# Interfaces_and_Connectors.net
KiCad netlist of a schematic drawn in Altium Designer
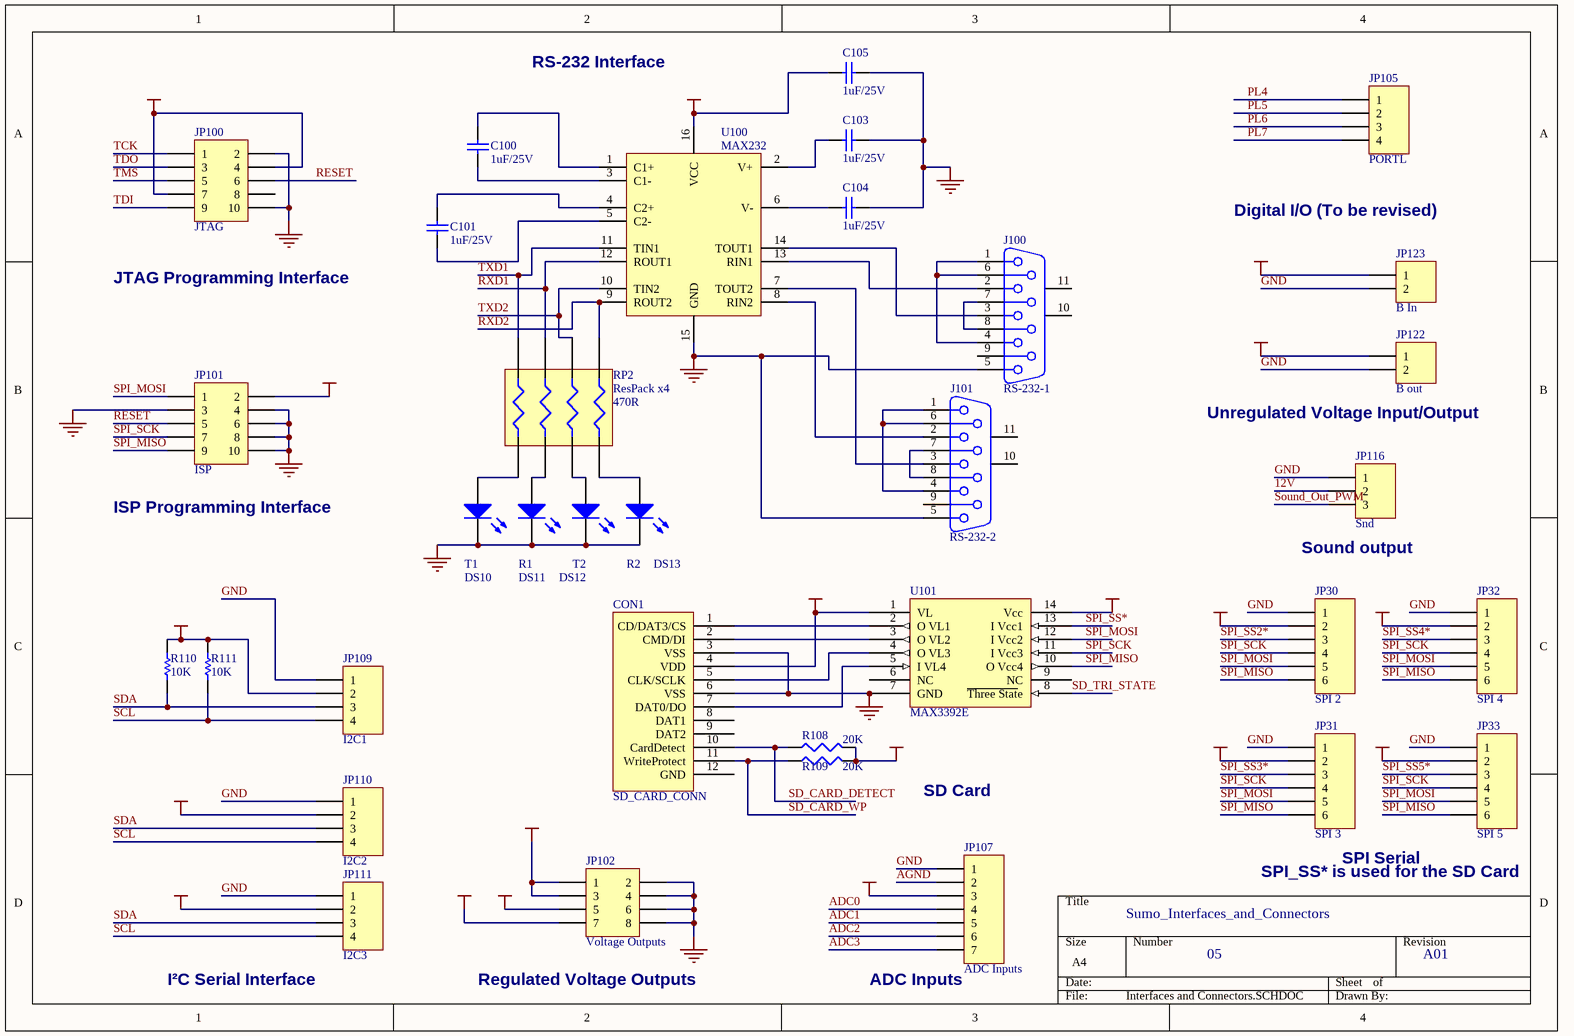
[diagram p0: Interfaces and Connectors.SCHDOC]

(export (version "E")
  (design (tool "Eeschema 10.0.6"))
  (components
    (comp (ref "C100")
      (value "1uF/25V")
      (footprint "CC2012-0805")
      (description "Capacitor (Semiconductor SIM Model)")
      (fields (field (name "Comment") "Cap Semi") (field (name "PUBLISHER") "Altium Limited"))
      (libsource (lib "Miscellaneous Devices") (part "Cap Semi"))
    )
    (comp (ref "C101")
      (value "1uF/25V")
      (footprint "CC2012-0805")
      (description "Capacitor (Semiconductor SIM Model)")
      (fields (field (name "Comment") "Cap Semi") (field (name "PUBLISHER") "Altium Limited"))
      (libsource (lib "Miscellaneous Devices") (part "Cap Semi"))
    )
    (comp (ref "C103")
      (value "1uF/25V")
      (footprint "CC2012-0805")
      (description "Capacitor (Semiconductor SIM Model)")
      (fields (field (name "Comment") "Cap Semi") (field (name "PUBLISHER") "Altium Limited"))
      (libsource (lib "Miscellaneous Devices") (part "Cap Semi"))
    )
    (comp (ref "C104")
      (value "1uF/25V")
      (footprint "CC2012-0805")
      (description "Capacitor (Semiconductor SIM Model)")
      (fields (field (name "Comment") "Cap Semi") (field (name "PUBLISHER") "Altium Limited"))
      (libsource (lib "Miscellaneous Devices") (part "Cap Semi"))
    )
    (comp (ref "C105")
      (value "1uF/25V")
      (footprint "CC2012-0805")
      (description "Capacitor (Semiconductor SIM Model)")
      (fields (field (name "Comment") "Cap Semi") (field (name "PUBLISHER") "Altium Limited"))
      (libsource (lib "Miscellaneous Devices") (part "Cap Semi"))
    )
    (comp (ref "CON1")
      (value "SD_CARD_CONN")
      (footprint "SD Card AVX")
      (libsource (lib "Sumo") (part "SD_CARD_CONN"))
    )
    (comp (ref "DS10")
      (value "T1")
      (footprint "SMD _LED")
      (description "Typical BLUE SiC LED")
      (fields (field (name "PUBLISHER") "Altium Limited"))
      (libsource (lib "Miscellaneous Devices") (part "LED3"))
    )
    (comp (ref "DS11")
      (value "R1")
      (footprint "SMD _LED")
      (description "Typical BLUE SiC LED")
      (fields (field (name "PUBLISHER") "Altium Limited"))
      (libsource (lib "Miscellaneous Devices") (part "LED3"))
    )
    (comp (ref "DS12")
      (value "T2")
      (footprint "SMD _LED")
      (description "Typical BLUE SiC LED")
      (fields (field (name "PUBLISHER") "Altium Limited"))
      (libsource (lib "Miscellaneous Devices") (part "LED3"))
    )
    (comp (ref "DS13")
      (value "R2")
      (footprint "SMD _LED")
      (description "Typical BLUE SiC LED")
      (fields (field (name "PUBLISHER") "Altium Limited"))
      (libsource (lib "Miscellaneous Devices") (part "LED3"))
    )
    (comp (ref "J100")
      (value "RS-232-1")
      (footprint "DSUB1.385-2H9 Simple")
      (description "Receptacle Assembly, 9 Position, Right Angle")
      (fields (field (name "PUBLISHER") "Altium Limited"))
      (libsource (lib "Miscellaneous Connectors") (part "D Connector 9"))
    )
    (comp (ref "J101")
      (value "RS-232-2")
      (footprint "DSUB1.385-2H9 Simple")
      (description "Receptacle Assembly, 9 Position, Right Angle")
      (fields (field (name "PUBLISHER") "Altium Limited"))
      (libsource (lib "Miscellaneous Connectors") (part "D Connector 9"))
    )
    (comp (ref "JP30")
      (value "SPI 2")
      (footprint "ZHR 1x6 1.5mm")
      (description "Header, 6-Pin")
      (fields (field (name "PUBLISHER") "Altium Limited"))
      (libsource (lib "Miscellaneous Connectors") (part "Header 6"))
    )
    (comp (ref "JP31")
      (value "SPI 3")
      (footprint "ZHR 1x6 1.5mm")
      (description "Header, 6-Pin")
      (fields (field (name "PUBLISHER") "Altium Limited"))
      (libsource (lib "Miscellaneous Connectors") (part "Header 6"))
    )
    (comp (ref "JP32")
      (value "SPI 4")
      (footprint "ZHR 1x6 1.5mm")
      (description "Header, 6-Pin")
      (fields (field (name "PUBLISHER") "Altium Limited"))
      (libsource (lib "Miscellaneous Connectors") (part "Header 6"))
    )
    (comp (ref "JP33")
      (value "SPI 5")
      (footprint "ZHR 1x6 1.5mm")
      (description "Header, 6-Pin")
      (fields (field (name "PUBLISHER") "Altium Limited"))
      (libsource (lib "Miscellaneous Connectors") (part "Header 6"))
    )
    (comp (ref "JP100")
      (value "JTAG")
      (footprint "HDR2X5")
      (description "Header, 5-Pin, Dual row")
      (fields (field (name "PUBLISHER") "Altium Limited"))
      (libsource (lib "Miscellaneous Connectors") (part "Header 5X2"))
    )
    (comp (ref "JP101")
      (value "ISP")
      (footprint "HDR2X5")
      (description "Header, 5-Pin, Dual row")
      (fields (field (name "PUBLISHER") "Altium Limited"))
      (libsource (lib "Miscellaneous Connectors") (part "Header 5X2"))
    )
    (comp (ref "JP102")
      (value "Voltage Outputs")
      (footprint "microfit 2x4 3mm")
      (description "Header, 4-Pin, Dual row")
      (fields (field (name "PUBLISHER") "Altium Limited"))
      (libsource (lib "Miscellaneous Connectors") (part "Header 4X2"))
    )
    (comp (ref "JP105")
      (value "PORTL")
      (footprint "EHR 1x4 2.5mm")
      (description "Header, 4-Pin")
      (fields (field (name "PUBLISHER") "Altium Limited"))
      (libsource (lib "Miscellaneous Connectors") (part "Header 4"))
    )
    (comp (ref "JP107")
      (value "ADC Inputs")
      (footprint "KK 1x7 2.54mm")
      (description "Header, 7-Pin")
      (fields (field (name "PUBLISHER") "Altium Limited"))
      (libsource (lib "Miscellaneous Connectors") (part "Header 7"))
    )
    (comp (ref "JP109")
      (value "I2C1")
      (footprint "ZHR 1x4 1.5mm")
      (description "Header, 4-Pin")
      (fields (field (name "PUBLISHER") "Altium Limited"))
      (libsource (lib "Miscellaneous Connectors") (part "Header 4"))
    )
    (comp (ref "JP110")
      (value "I2C2")
      (footprint "ZHR 1x4 1.5mm")
      (description "Header, 4-Pin")
      (fields (field (name "PUBLISHER") "Altium Limited"))
      (libsource (lib "Miscellaneous Connectors") (part "Header 4"))
    )
    (comp (ref "JP111")
      (value "I2C3")
      (footprint "ZHR 1x4 1.5mm")
      (description "Header, 4-Pin")
      (fields (field (name "PUBLISHER") "Altium Limited"))
      (libsource (lib "Miscellaneous Connectors") (part "Header 4"))
    )
    (comp (ref "JP116")
      (value "Snd")
      (footprint "KK 1x3 2.54mm")
      (description "Header, 3-Pin")
      (fields (field (name "PUBLISHER") "Altium Limited"))
      (libsource (lib "Miscellaneous Connectors") (part "Header 3"))
    )
    (comp (ref "JP122")
      (value "B out")
      (footprint "Mini-Fit Jnr 2x1 4.2mm")
      (description "Header, 2-Pin")
      (fields (field (name "PUBLISHER") "Altium Limited"))
      (libsource (lib "Miscellaneous Connectors") (part "Header 2"))
    )
    (comp (ref "JP123")
      (value "B In")
      (footprint "Mini-Fit Jnr 2x1 4.2mm")
      (description "Header, 2-Pin")
      (fields (field (name "PUBLISHER") "Altium Limited"))
      (libsource (lib "Miscellaneous Connectors") (part "Header 2"))
    )
    (comp (ref "R108")
      (value "20K")
      (footprint "CR2012-0805")
      (description "Resistor")
      (fields (field (name "Comment") "Res3") (field (name "PUBLISHER") "Altium Limited"))
      (libsource (lib "Miscellaneous Devices") (part "Res3"))
    )
    (comp (ref "R109")
      (value "20K")
      (footprint "CR2012-0805")
      (description "Resistor")
      (fields (field (name "Comment") "Res3") (field (name "PUBLISHER") "Altium Limited"))
      (libsource (lib "Miscellaneous Devices") (part "Res3"))
    )
    (comp (ref "R110")
      (value "10K")
      (footprint "CR2012-0805")
      (description "Resistor")
      (fields (field (name "PUBLISHER") "Altium Limited"))
      (libsource (lib "Miscellaneous Devices") (part "Res1"))
    )
    (comp (ref "R111")
      (value "10K")
      (footprint "CR2012-0805")
      (description "Resistor")
      (fields (field (name "PUBLISHER") "Altium Limited"))
      (libsource (lib "Miscellaneous Devices") (part "Res1"))
    )
    (comp (ref "RP2")
      (value "ResPack x4")
      (footprint "4x0603 Resistor pack")
      (fields (field (name "ALTIUM_VALUE") "470R"))
      (libsource (lib "Sumo") (part "ResPack x4"))
    )
    (comp (ref "U100")
      (value "MAX232")
      (footprint "SO-G16/C5.85")
      (description "Maxim RS-232 Transceiver")
      (libsource (lib "Sumo") (part "MAX232"))
    )
    (comp (ref "U101") (value "MAX3392E") (footprint "TSSOP14") (libsource (lib "Sumo") (part "MAX3392E")))
  )
  (nets
    (net (code "1") (name "/ADC0") (class "Default")
      (node (ref "JP107") (pin "4") (pinfunction "4_4") (pintype "passive"))
    )
    (net (code "2") (name "/ADC1") (class "Default")
      (node (ref "JP107") (pin "5") (pinfunction "5_5") (pintype "passive"))
    )
    (net (code "3") (name "/ADC2") (class "Default")
      (node (ref "JP107") (pin "6") (pinfunction "6_6") (pintype "passive"))
    )
    (net (code "4") (name "/ADC3") (class "Default")
      (node (ref "JP107") (pin "7") (pinfunction "7_7") (pintype "passive"))
    )
    (net (code "5") (name "/AGND") (class "Default")
      (node (ref "JP107") (pin "2") (pinfunction "2_2") (pintype "passive"))
    )
    (net (code "6") (name "/PL4") (class "Default")
      (node (ref "JP105") (pin "1") (pinfunction "1_1") (pintype "passive"))
    )
    (net (code "7") (name "/PL5") (class "Default")
      (node (ref "JP105") (pin "2") (pinfunction "2_2") (pintype "passive"))
    )
    (net (code "8") (name "/PL6") (class "Default")
      (node (ref "JP105") (pin "3") (pinfunction "3_3") (pintype "passive"))
    )
    (net (code "9") (name "/PL7") (class "Default")
      (node (ref "JP105") (pin "4") (pinfunction "4_4") (pintype "passive"))
    )
    (net (code "10") (name "/RESET") (class "Default")
      (node (ref "JP100") (pin "6") (pinfunction "6_6") (pintype "passive"))
      (node (ref "JP101") (pin "5") (pinfunction "5_5") (pintype "passive"))
    )
    (net (code "11") (name "/RXD1") (class "Default")
      (node (ref "RP2") (pin "7") (pintype "passive"))
      (node (ref "U100") (pin "12") (pinfunction "ROUT1_12") (pintype "passive"))
    )
    (net (code "12") (name "/RXD2") (class "Default")
      (node (ref "RP2") (pin "5") (pintype "passive"))
      (node (ref "U100") (pin "9") (pinfunction "ROUT2_9") (pintype "passive"))
    )
    (net (code "13") (name "/SCL") (class "Default")
      (node (ref "JP109") (pin "4") (pinfunction "4_4") (pintype "passive"))
      (node (ref "JP110") (pin "4") (pinfunction "4_4") (pintype "passive"))
      (node (ref "JP111") (pin "4") (pinfunction "4_4") (pintype "passive"))
      (node (ref "R111") (pin "1") (pinfunction "1_1") (pintype "passive"))
    )
    (net (code "14") (name "/SDA") (class "Default")
      (node (ref "JP109") (pin "3") (pinfunction "3_3") (pintype "passive"))
      (node (ref "JP110") (pin "3") (pinfunction "3_3") (pintype "passive"))
      (node (ref "JP111") (pin "3") (pinfunction "3_3") (pintype "passive"))
      (node (ref "R110") (pin "1") (pinfunction "1_1") (pintype "passive"))
    )
    (net (code "15") (name "/SD_CARD_DETECT") (class "Default")
      (node (ref "CON1") (pin "10") (pinfunction "CardDetect_10") (pintype "passive"))
      (node (ref "R108") (pin "1") (pinfunction "1_1") (pintype "passive"))
    )
    (net (code "16") (name "/SD_CARD_WP") (class "Default")
      (node (ref "CON1") (pin "11") (pinfunction "WriteProtect_11") (pintype "passive"))
      (node (ref "R109") (pin "1") (pinfunction "1_1") (pintype "passive"))
    )
    (net (code "17") (name "/SD_TRI_STATE") (class "Default")
      (node (ref "U101") (pin "8") (pinfunction "~{Three_Stat}e_8") (pintype "input"))
    )
    (net (code "18") (name "/SPI_MISO") (class "Default")
      (node (ref "JP101") (pin "9") (pinfunction "9_9") (pintype "passive"))
      (node (ref "JP30") (pin "6") (pinfunction "6_6") (pintype "passive"))
      (node (ref "JP31") (pin "6") (pinfunction "6_6") (pintype "passive"))
      (node (ref "JP32") (pin "6") (pinfunction "6_6") (pintype "passive"))
      (node (ref "JP33") (pin "6") (pinfunction "6_6") (pintype "passive"))
      (node (ref "U101") (pin "10") (pinfunction "O_Vcc4_10") (pintype "output"))
    )
    (net (code "19") (name "/SPI_MOSI") (class "Default")
      (node (ref "JP101") (pin "1") (pinfunction "1_1") (pintype "passive"))
      (node (ref "JP30") (pin "5") (pinfunction "5_5") (pintype "passive"))
      (node (ref "JP31") (pin "5") (pinfunction "5_5") (pintype "passive"))
      (node (ref "JP32") (pin "5") (pinfunction "5_5") (pintype "passive"))
      (node (ref "JP33") (pin "5") (pinfunction "5_5") (pintype "passive"))
      (node (ref "U101") (pin "12") (pinfunction "I_Vcc2_12") (pintype "input"))
    )
    (net (code "20") (name "/SPI_SCK") (class "Default")
      (node (ref "JP101") (pin "7") (pinfunction "7_7") (pintype "passive"))
      (node (ref "JP30") (pin "4") (pinfunction "4_4") (pintype "passive"))
      (node (ref "JP31") (pin "4") (pinfunction "4_4") (pintype "passive"))
      (node (ref "JP32") (pin "4") (pinfunction "4_4") (pintype "passive"))
      (node (ref "JP33") (pin "4") (pinfunction "4_4") (pintype "passive"))
      (node (ref "U101") (pin "11") (pinfunction "I_Vcc3_11") (pintype "input"))
    )
    (net (code "21") (name "/SPI_SS*") (class "Default")
      (node (ref "U101") (pin "13") (pinfunction "I_Vcc1_13") (pintype "input"))
    )
    (net (code "22") (name "/SPI_SS2*") (class "Default")
      (node (ref "JP30") (pin "3") (pinfunction "3_3") (pintype "passive"))
    )
    (net (code "23") (name "/SPI_SS3*") (class "Default")
      (node (ref "JP31") (pin "3") (pinfunction "3_3") (pintype "passive"))
    )
    (net (code "24") (name "/SPI_SS4*") (class "Default")
      (node (ref "JP32") (pin "3") (pinfunction "3_3") (pintype "passive"))
    )
    (net (code "25") (name "/SPI_SS5*") (class "Default")
      (node (ref "JP33") (pin "3") (pinfunction "3_3") (pintype "passive"))
    )
    (net (code "26") (name "/Sound_Out_PWM") (class "Default")
      (node (ref "JP116") (pin "3") (pinfunction "3_3") (pintype "passive"))
    )
    (net (code "27") (name "/TCK") (class "Default")
      (node (ref "JP100") (pin "1") (pinfunction "1_1") (pintype "passive"))
    )
    (net (code "28") (name "/TDI") (class "Default")
      (node (ref "JP100") (pin "9") (pinfunction "9_9") (pintype "passive"))
    )
    (net (code "29") (name "/TDO") (class "Default")
      (node (ref "JP100") (pin "3") (pinfunction "3_3") (pintype "passive"))
    )
    (net (code "30") (name "/TMS") (class "Default")
      (node (ref "JP100") (pin "5") (pinfunction "5_5") (pintype "passive"))
    )
    (net (code "31") (name "/TXD1") (class "Default")
      (node (ref "RP2") (pin "8") (pintype "passive"))
      (node (ref "U100") (pin "11") (pinfunction "TIN1_11") (pintype "passive"))
    )
    (net (code "32") (name "/TXD2") (class "Default")
      (node (ref "RP2") (pin "6") (pintype "passive"))
      (node (ref "U100") (pin "10") (pinfunction "TIN2_10") (pintype "passive"))
    )
    (net (code "33") (name "3V3") (class "Default")
      (node (ref "CON1") (pin "4") (pinfunction "VDD_4") (pintype "passive"))
      (node (ref "JP102") (pin "7") (pinfunction "7_7") (pintype "passive"))
      (node (ref "U101") (pin "1") (pinfunction "VL_1") (pintype "power_in"))
    )
    (net (code "34") (name "5V") (class "Default")
      (node (ref "C105") (pin "1") (pinfunction "1_1") (pintype "passive"))
      (node (ref "JP100") (pin "4") (pinfunction "4_4") (pintype "passive"))
      (node (ref "JP100") (pin "7") (pinfunction "7_7") (pintype "passive"))
      (node (ref "JP101") (pin "2") (pinfunction "2_2") (pintype "passive"))
      (node (ref "JP102") (pin "5") (pinfunction "5_5") (pintype "passive"))
      (node (ref "JP107") (pin "3") (pinfunction "3_3") (pintype "passive"))
      (node (ref "JP109") (pin "2") (pinfunction "2_2") (pintype "passive"))
      (node (ref "JP110") (pin "2") (pinfunction "2_2") (pintype "passive"))
      (node (ref "JP111") (pin "2") (pinfunction "2_2") (pintype "passive"))
      (node (ref "JP30") (pin "2") (pinfunction "2_2") (pintype "passive"))
      (node (ref "JP31") (pin "2") (pinfunction "2_2") (pintype "passive"))
      (node (ref "JP32") (pin "2") (pinfunction "2_2") (pintype "passive"))
      (node (ref "JP33") (pin "2") (pinfunction "2_2") (pintype "passive"))
      (node (ref "R108") (pin "2") (pinfunction "2_2") (pintype "passive"))
      (node (ref "R109") (pin "2") (pinfunction "2_2") (pintype "passive"))
      (node (ref "R110") (pin "2") (pinfunction "2_2") (pintype "passive"))
      (node (ref "R111") (pin "2") (pinfunction "2_2") (pintype "passive"))
      (node (ref "U100") (pin "16") (pinfunction "VCC_16") (pintype "passive"))
      (node (ref "U101") (pin "14") (pinfunction "Vcc_14") (pintype "power_in"))
    )
    (net (code "35") (name "12V") (class "Default")
      (node (ref "JP102") (pin "1") (pinfunction "1_1") (pintype "passive"))
      (node (ref "JP102") (pin "3") (pinfunction "3_3") (pintype "passive"))
      (node (ref "JP116") (pin "2") (pinfunction "2_2") (pintype "passive"))
    )
    (net (code "36") (name "GND") (class "Default")
      (node (ref "C103") (pin "2") (pinfunction "2_2") (pintype "passive"))
      (node (ref "C104") (pin "2") (pinfunction "2_2") (pintype "passive"))
      (node (ref "C105") (pin "2") (pinfunction "2_2") (pintype "passive"))
      (node (ref "CON1") (pin "3") (pinfunction "VSS_3") (pintype "passive"))
      (node (ref "CON1") (pin "6") (pinfunction "VSS_6") (pintype "passive"))
      (node (ref "DS10") (pin "2") (pinfunction "K_2") (pintype "passive"))
      (node (ref "DS11") (pin "2") (pinfunction "K_2") (pintype "passive"))
      (node (ref "DS12") (pin "2") (pinfunction "K_2") (pintype "passive"))
      (node (ref "DS13") (pin "2") (pinfunction "K_2") (pintype "passive"))
      (node (ref "J100") (pin "5") (pinfunction "5_5") (pintype "passive"))
      (node (ref "J101") (pin "5") (pinfunction "5_5") (pintype "passive"))
      (node (ref "JP100") (pin "10") (pinfunction "10_10") (pintype "passive"))
      (node (ref "JP100") (pin "2") (pinfunction "2_2") (pintype "passive"))
      (node (ref "JP101") (pin "10") (pinfunction "10_10") (pintype "passive"))
      (node (ref "JP101") (pin "3") (pinfunction "3_3") (pintype "passive"))
      (node (ref "JP101") (pin "4") (pinfunction "4_4") (pintype "passive"))
      (node (ref "JP101") (pin "6") (pinfunction "6_6") (pintype "passive"))
      (node (ref "JP101") (pin "8") (pinfunction "8_8") (pintype "passive"))
      (node (ref "JP102") (pin "2") (pinfunction "2_2") (pintype "passive"))
      (node (ref "JP102") (pin "4") (pinfunction "4_4") (pintype "passive"))
      (node (ref "JP102") (pin "6") (pinfunction "6_6") (pintype "passive"))
      (node (ref "JP102") (pin "8") (pinfunction "8_8") (pintype "passive"))
      (node (ref "JP107") (pin "1") (pinfunction "1_1") (pintype "passive"))
      (node (ref "JP109") (pin "1") (pinfunction "1_1") (pintype "passive"))
      (node (ref "JP110") (pin "1") (pinfunction "1_1") (pintype "passive"))
      (node (ref "JP111") (pin "1") (pinfunction "1_1") (pintype "passive"))
      (node (ref "JP116") (pin "1") (pinfunction "1_1") (pintype "passive"))
      (node (ref "JP122") (pin "2") (pinfunction "2_2") (pintype "passive"))
      (node (ref "JP123") (pin "2") (pinfunction "2_2") (pintype "passive"))
      (node (ref "JP30") (pin "1") (pinfunction "1_1") (pintype "passive"))
      (node (ref "JP31") (pin "1") (pinfunction "1_1") (pintype "passive"))
      (node (ref "JP32") (pin "1") (pinfunction "1_1") (pintype "passive"))
      (node (ref "JP33") (pin "1") (pinfunction "1_1") (pintype "passive"))
      (node (ref "U100") (pin "15") (pinfunction "GND_15") (pintype "passive"))
      (node (ref "U101") (pin "7") (pinfunction "GND_7") (pintype "power_in"))
    )
    (net (code "37") (name "Net-(CON1-CD{slash}DAT3{slash}CS)") (class "Default")
      (node (ref "CON1") (pin "1") (pinfunction "CD/DAT3/CS_1") (pintype "passive"))
      (node (ref "U101") (pin "2") (pinfunction "O_VL1_2") (pintype "output"))
    )
    (net (code "38") (name "Net-(CON1-CLK{slash}SCLK)") (class "Default")
      (node (ref "CON1") (pin "5") (pinfunction "CLK/SCLK_5") (pintype "passive"))
      (node (ref "U101") (pin "4") (pinfunction "O_VL3_4") (pintype "output"))
    )
    (net (code "39") (name "Net-(CON1-CMD{slash}DI)") (class "Default")
      (node (ref "CON1") (pin "2") (pinfunction "CMD/DI_2") (pintype "passive"))
      (node (ref "U101") (pin "3") (pinfunction "O_VL2_3") (pintype "output"))
    )
    (net (code "40") (name "Net-(CON1-DAT0{slash}DO)") (class "Default")
      (node (ref "CON1") (pin "7") (pinfunction "DAT0/DO_7") (pintype "passive"))
      (node (ref "U101") (pin "5") (pinfunction "I_VL4_5") (pintype "input"))
    )
    (net (code "41") (name "Net-(DS10-A)") (class "Default")
      (node (ref "DS10") (pin "1") (pinfunction "A_1") (pintype "passive"))
      (node (ref "RP2") (pin "1") (pintype "passive"))
    )
    (net (code "42") (name "Net-(DS11-A)") (class "Default")
      (node (ref "DS11") (pin "1") (pinfunction "A_1") (pintype "passive"))
      (node (ref "RP2") (pin "2") (pintype "passive"))
    )
    (net (code "43") (name "Net-(DS12-A)") (class "Default")
      (node (ref "DS12") (pin "1") (pinfunction "A_1") (pintype "passive"))
      (node (ref "RP2") (pin "3") (pintype "passive"))
    )
    (net (code "44") (name "Net-(DS13-A)") (class "Default")
      (node (ref "DS13") (pin "1") (pinfunction "A_1") (pintype "passive"))
      (node (ref "RP2") (pin "4") (pintype "passive"))
    )
    (net (code "45") (name "Net-(J100-Pad1)") (class "Default")
      (node (ref "J100") (pin "1") (pinfunction "1_1") (pintype "passive"))
      (node (ref "J100") (pin "4") (pinfunction "4_4") (pintype "passive"))
      (node (ref "J100") (pin "6") (pinfunction "6_6") (pintype "passive"))
    )
    (net (code "46") (name "Net-(J100-Pad7)") (class "Default")
      (node (ref "J100") (pin "7") (pinfunction "7_7") (pintype "passive"))
      (node (ref "J100") (pin "8") (pinfunction "8_8") (pintype "passive"))
    )
    (net (code "47") (name "Net-(J101-Pad1)") (class "Default")
      (node (ref "J101") (pin "1") (pinfunction "1_1") (pintype "passive"))
      (node (ref "J101") (pin "4") (pinfunction "4_4") (pintype "passive"))
      (node (ref "J101") (pin "6") (pinfunction "6_6") (pintype "passive"))
    )
    (net (code "48") (name "Net-(J101-Pad7)") (class "Default")
      (node (ref "J101") (pin "7") (pinfunction "7_7") (pintype "passive"))
      (node (ref "J101") (pin "8") (pinfunction "8_8") (pintype "passive"))
    )
    (net (code "49") (name "Net-(U100-C1+)") (class "Default")
      (node (ref "C100") (pin "2") (pinfunction "2_2") (pintype "passive"))
      (node (ref "U100") (pin "1") (pinfunction "C1+_1") (pintype "passive"))
    )
    (net (code "50") (name "Net-(U100-C1-)") (class "Default")
      (node (ref "C100") (pin "1") (pinfunction "1_1") (pintype "passive"))
      (node (ref "U100") (pin "3") (pinfunction "C1-_3") (pintype "passive"))
    )
    (net (code "51") (name "Net-(U100-C2+)") (class "Default")
      (node (ref "C101") (pin "2") (pinfunction "2_2") (pintype "passive"))
      (node (ref "U100") (pin "4") (pinfunction "C2+_4") (pintype "passive"))
    )
    (net (code "52") (name "Net-(U100-C2-)") (class "Default")
      (node (ref "C101") (pin "1") (pinfunction "1_1") (pintype "passive"))
      (node (ref "U100") (pin "5") (pinfunction "C2-_5") (pintype "passive"))
    )
    (net (code "53") (name "Net-(U100-RIN1)") (class "Default")
      (node (ref "J100") (pin "2") (pinfunction "2_2") (pintype "passive"))
      (node (ref "U100") (pin "13") (pinfunction "RIN1_13") (pintype "passive"))
    )
    (net (code "54") (name "Net-(U100-RIN2)") (class "Default")
      (node (ref "J101") (pin "2") (pinfunction "2_2") (pintype "passive"))
      (node (ref "U100") (pin "8") (pinfunction "RIN2_8") (pintype "passive"))
    )
    (net (code "55") (name "Net-(U100-TOUT1)") (class "Default")
      (node (ref "J100") (pin "3") (pinfunction "3_3") (pintype "passive"))
      (node (ref "U100") (pin "14") (pinfunction "TOUT1_14") (pintype "passive"))
    )
    (net (code "56") (name "Net-(U100-TOUT2)") (class "Default")
      (node (ref "J101") (pin "3") (pinfunction "3_3") (pintype "passive"))
      (node (ref "U100") (pin "7") (pinfunction "TOUT2_7") (pintype "passive"))
    )
    (net (code "57") (name "Net-(U100-V+)") (class "Default")
      (node (ref "C103") (pin "1") (pinfunction "1_1") (pintype "passive"))
      (node (ref "U100") (pin "2") (pinfunction "V+_2") (pintype "passive"))
    )
    (net (code "58") (name "Net-(U100-V-)") (class "Default")
      (node (ref "C104") (pin "1") (pinfunction "1_1") (pintype "passive"))
      (node (ref "U100") (pin "6") (pinfunction "V-_6") (pintype "passive"))
    )
    (net (code "59") (name "VBat") (class "Default")
      (node (ref "JP122") (pin "1") (pinfunction "1_1") (pintype "passive"))
    )
    (net (code "60") (name "VBatIn") (class "Default")
      (node (ref "JP123") (pin "1") (pinfunction "1_1") (pintype "passive"))
    )
    (net (code "61") (name "unconnected-(CON1-DAT1-Pad8)") (class "Default")
      (node (ref "CON1") (pin "8") (pinfunction "DAT1_8") (pintype "passive"))
    )
    (net (code "62") (name "unconnected-(CON1-DAT2-Pad9)") (class "Default")
      (node (ref "CON1") (pin "9") (pinfunction "DAT2_9") (pintype "passive"))
    )
    (net (code "63") (name "unconnected-(CON1-GND-Pad12)") (class "Default")
      (node (ref "CON1") (pin "12") (pinfunction "GND_12") (pintype "passive"))
    )
    (net (code "64") (name "unconnected-(J100-MH1-Pad10)") (class "Default")
      (node (ref "J100") (pin "10") (pinfunction "MH1_10") (pintype "passive"))
    )
    (net (code "65") (name "unconnected-(J100-MH2-Pad11)") (class "Default")
      (node (ref "J100") (pin "11") (pinfunction "MH2_11") (pintype "passive"))
    )
    (net (code "66") (name "unconnected-(J100-Pad9)") (class "Default")
      (node (ref "J100") (pin "9") (pinfunction "9_9") (pintype "passive"))
    )
    (net (code "67") (name "unconnected-(J101-MH1-Pad10)") (class "Default")
      (node (ref "J101") (pin "10") (pinfunction "MH1_10") (pintype "passive"))
    )
    (net (code "68") (name "unconnected-(J101-MH2-Pad11)") (class "Default")
      (node (ref "J101") (pin "11") (pinfunction "MH2_11") (pintype "passive"))
    )
    (net (code "69") (name "unconnected-(J101-Pad9)") (class "Default")
      (node (ref "J101") (pin "9") (pinfunction "9_9") (pintype "passive"))
    )
    (net (code "70") (name "unconnected-(JP100-Pad8)") (class "Default")
      (node (ref "JP100") (pin "8") (pinfunction "8_8") (pintype "passive"))
    )
    (net (code "71") (name "unconnected-(U101-NC-Pad6)") (class "Default")
      (node (ref "U101") (pin "6") (pinfunction "NC_6") (pintype "passive"))
    )
    (net (code "72") (name "unconnected-(U101-NC-Pad9)") (class "Default")
      (node (ref "U101") (pin "9") (pinfunction "NC_9") (pintype "passive"))
    )
  )
)
